# power_sw.net
KiCad netlist of a schematic drawn in Altium Designer
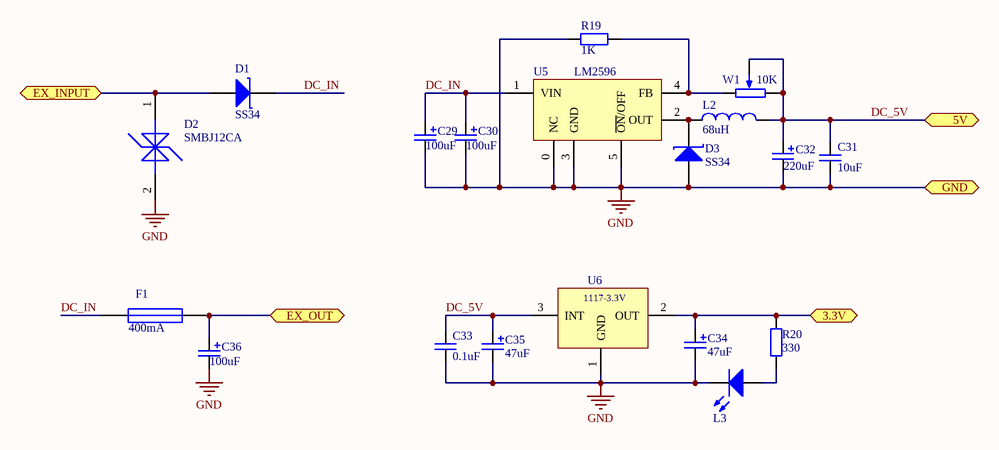
[diagram p0: power_sw.SchDoc]

(export (version "E")
  (design (tool "Eeschema 10.0.6"))
  (components
    (comp (ref "C29")
      (value "100uF")
      (footprint "ECAP_S")
      (fields (field (name "Comment") "CAP 330uF"))
      (libsource (lib "Schlib1") (part "CAP 330uF"))
    )
    (comp (ref "C30")
      (value "100uF")
      (footprint "ECAP_S")
      (fields (field (name "Comment") "CAP 330uF"))
      (libsource (lib "Schlib1") (part "CAP 330uF"))
    )
    (comp (ref "C31")
      (value "10uF")
      (footprint "CAP-0805")
      (fields (field (name "Comment") "CAP"))
      (libsource (lib "Schlib1") (part "CAP"))
    )
    (comp (ref "C32")
      (value "220uF")
      (footprint "ECAP_S")
      (fields (field (name "Comment") "CAP 330uF"))
      (libsource (lib "Schlib1") (part "CAP 330uF"))
    )
    (comp (ref "C33")
      (value "0.1uF")
      (footprint "CAP-0805")
      (fields (field (name "Comment") "CAP"))
      (libsource (lib "Schlib1") (part "CAP"))
    )
    (comp (ref "C34")
      (value "47uF")
      (footprint "CAP_B")
      (fields (field (name "Comment") "CAP 10UF"))
      (libsource (lib "Schlib1") (part "CAP 10UF"))
    )
    (comp (ref "C35")
      (value "47uF")
      (footprint "CAP_B")
      (fields (field (name "Comment") "CAP 10UF"))
      (libsource (lib "Schlib1") (part "CAP 10UF"))
    )
    (comp (ref "C36")
      (value "100uF")
      (footprint "ECAP_S")
      (fields (field (name "Comment") "CAP 330uF"))
      (libsource (lib "Schlib1") (part "CAP 330uF"))
    )
    (comp (ref "D1") (value "SS34") (footprint "DO214AC") (libsource (lib "Schlib1") (part "SS34")))
    (comp (ref "D2") (value "SMBJ12CA") (footprint "DO214AB") (libsource (lib "Schlib1") (part "SMBJ30CA")))
    (comp (ref "D3") (value "SS34") (footprint "DO214AC") (libsource (lib "Schlib1") (part "SS34")))
    (comp (ref "F1") (value "400mA") (footprint "MF_R030") (libsource (lib "Schlib1") (part "MF_R030")))
    (comp (ref "L2")
      (value "68uH")
      (footprint "PWR_L")
      (fields (field (name "Comment") "INDUCTOR"))
      (libsource (lib "Schlib1") (part "INDUCTOR"))
    )
    (comp (ref "L3") (value "LED") (footprint "LED-0805") (libsource (lib "Schlib1") (part "LED")))
    (comp (ref "R19")
      (value "1K")
      (footprint "RES-0805")
      (fields (field (name "Comment") "RES"))
      (libsource (lib "Schlib1") (part "RES"))
    )
    (comp (ref "R20")
      (value "330")
      (footprint "RES-0805")
      (fields (field (name "Comment") "RES"))
      (libsource (lib "") (part "RES_1"))
    )
    (comp (ref "U5") (value "LM2596") (footprint "TO263") (libsource (lib "Schlib1") (part "LM2576/96")))
    (comp (ref "U6")
      (value "AMS117-3V3")
      (footprint "AMS1117")
      (libsource (lib "Schlib1") (part "AMS117-3V3"))
    )
    (comp (ref "W1")
      (value "10K")
      (footprint "RESPOT1")
      (fields (field (name "Comment") "RESPOT"))
      (libsource (lib "Schlib1") (part "RESPOT"))
    )
  )
  (nets
    (net (code "1") (name "/3.3V") (class "Default")
      (node (ref "C34") (pin "1") (pintype "passive"))
      (node (ref "R20") (pin "2") (pintype "passive"))
      (node (ref "U6") (pin "2") (pinfunction "OUT_2") (pintype "passive"))
    )
    (net (code "2") (name "/DC_5V") (class "Default")
      (node (ref "C31") (pin "2") (pintype "passive"))
      (node (ref "C32") (pin "1") (pintype "passive"))
      (node (ref "C33") (pin "2") (pintype "passive"))
      (node (ref "C35") (pin "1") (pintype "passive"))
      (node (ref "L2") (pin "2") (pinfunction "2_2") (pintype "passive"))
      (node (ref "U6") (pin "3") (pinfunction "INT_3") (pintype "passive"))
      (node (ref "W1") (pin "2") (pintype "passive"))
      (node (ref "W1") (pin "3") (pintype "passive"))
    )
    (net (code "3") (name "/DC_IN") (class "Default")
      (node (ref "C29") (pin "1") (pintype "passive"))
      (node (ref "C30") (pin "1") (pintype "passive"))
      (node (ref "D1") (pin "2") (pintype "passive"))
      (node (ref "F1") (pin "1") (pinfunction "1_1") (pintype "passive"))
      (node (ref "U5") (pin "1") (pinfunction "VIN_1") (pintype "passive"))
    )
    (net (code "4") (name "/EX_INPUT") (class "Default")
      (node (ref "D1") (pin "1") (pintype "passive"))
      (node (ref "D2") (pin "1") (pinfunction "1_1") (pintype "passive"))
    )
    (net (code "5") (name "/EX_OUT") (class "Default")
      (node (ref "C36") (pin "1") (pintype "passive"))
      (node (ref "F1") (pin "2") (pinfunction "2_2") (pintype "passive"))
    )
    (net (code "6") (name "GND") (class "Default")
      (node (ref "C29") (pin "2") (pintype "passive"))
      (node (ref "C30") (pin "2") (pintype "passive"))
      (node (ref "C31") (pin "1") (pintype "passive"))
      (node (ref "C32") (pin "2") (pintype "passive"))
      (node (ref "C33") (pin "1") (pintype "passive"))
      (node (ref "C34") (pin "2") (pintype "passive"))
      (node (ref "C35") (pin "2") (pintype "passive"))
      (node (ref "C36") (pin "2") (pintype "passive"))
      (node (ref "D2") (pin "2") (pinfunction "2_2") (pintype "passive"))
      (node (ref "D3") (pin "1") (pintype "passive"))
      (node (ref "L3") (pin "2") (pintype "passive"))
      (node (ref "R19") (pin "1") (pintype "passive"))
      (node (ref "U5") (pin "0") (pinfunction "NC_0") (pintype "passive"))
      (node (ref "U5") (pin "3") (pinfunction "GND_3") (pintype "passive"))
      (node (ref "U5") (pin "5") (pinfunction "~{ON}/OFF_5") (pintype "passive"))
      (node (ref "U6") (pin "1") (pinfunction "GND_1") (pintype "passive"))
    )
    (net (code "7") (name "Net-(L3-Pad1)") (class "Default")
      (node (ref "L3") (pin "1") (pintype "passive"))
      (node (ref "R20") (pin "1") (pintype "passive"))
    )
    (net (code "8") (name "Net-(U5-FB)") (class "Default")
      (node (ref "R19") (pin "2") (pintype "passive"))
      (node (ref "U5") (pin "4") (pinfunction "FB_4") (pintype "passive"))
      (node (ref "W1") (pin "1") (pintype "passive"))
    )
    (net (code "9") (name "Net-(U5-OUT)") (class "Default")
      (node (ref "D3") (pin "2") (pintype "passive"))
      (node (ref "L2") (pin "1") (pinfunction "1_1") (pintype "passive"))
      (node (ref "U5") (pin "2") (pinfunction "OUT_2") (pintype "passive"))
    )
  )
)
